# Stenophone.net
KiCad netlist of a schematic drawn in EAGLE
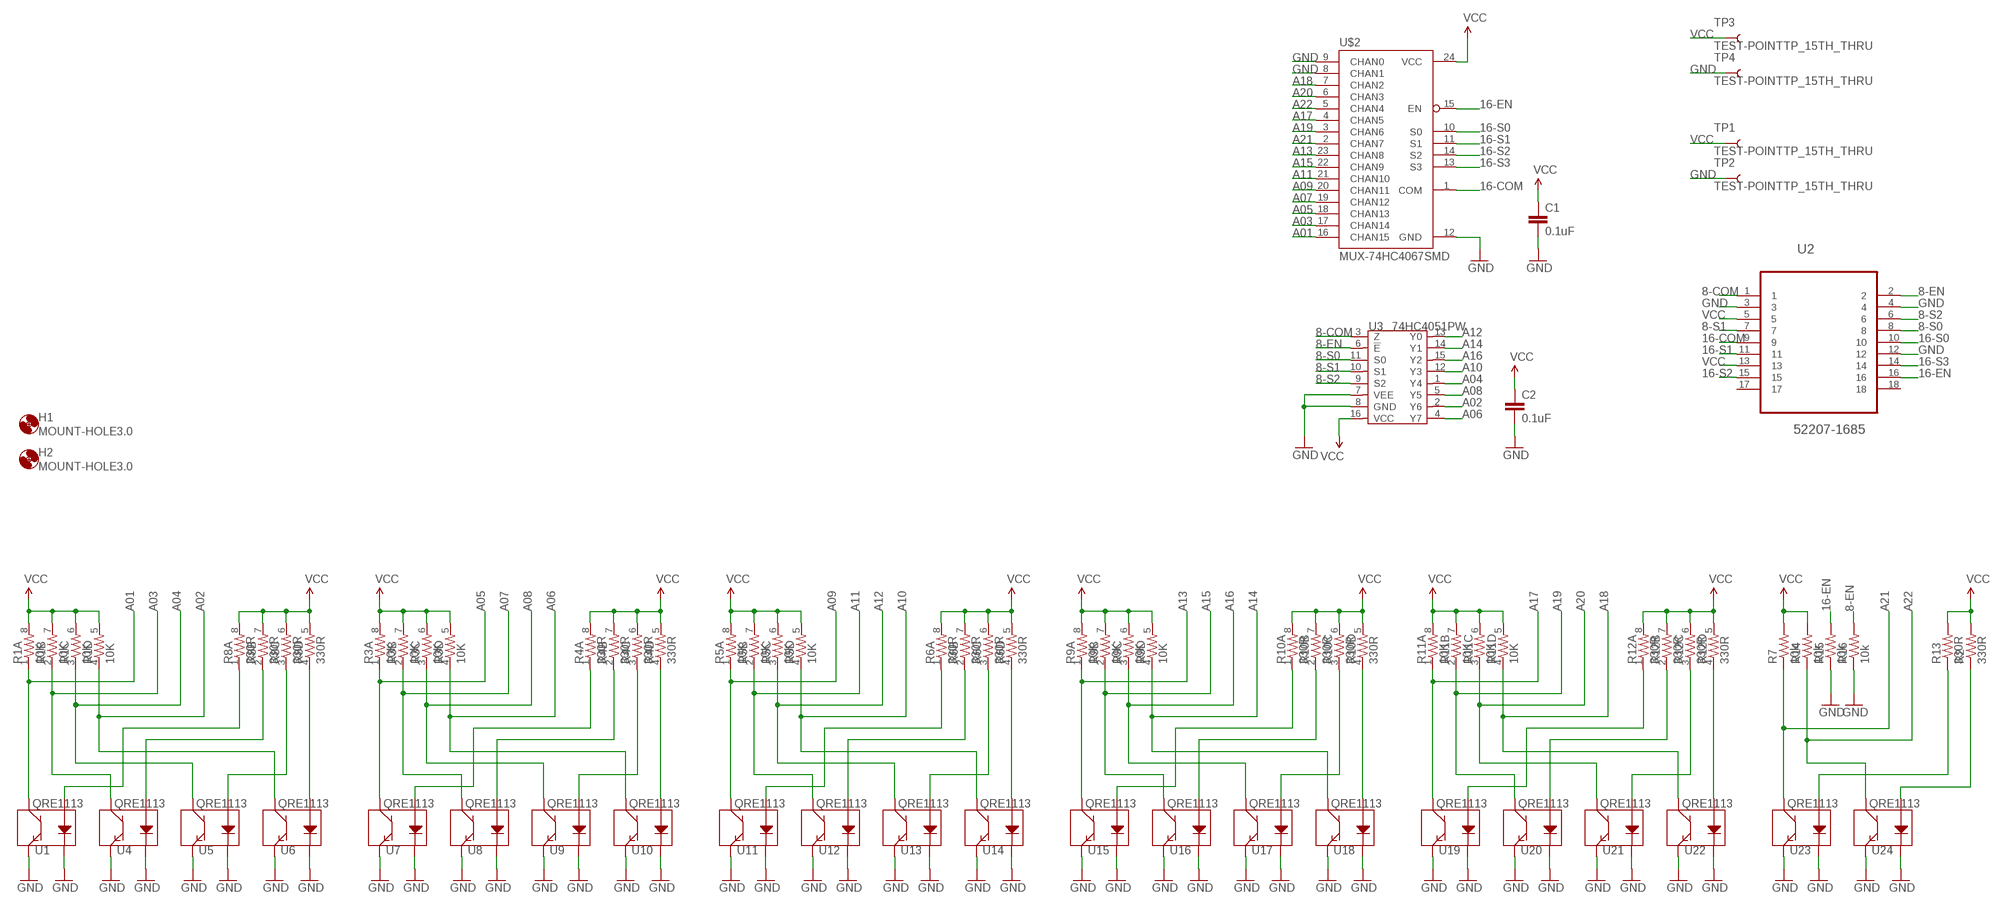
[diagram p0: schematic, sheet 1]

(export (version "E")
  (design (tool "Eeschema 10.0.6"))
  (components
    (comp (ref "C1")
      (value "0.1uF")
      (footprint "eagle-import:0603-CAP")
      (libsource (lib "eagle-import") (part "CAP0603-CAP"))
    )
    (comp (ref "C2")
      (value "0.1uF")
      (footprint "eagle-import:0603-CAP")
      (libsource (lib "eagle-import") (part "CAP0603-CAP"))
    )
    (comp (ref "H1")
      (value "MOUNT-HOLE3.0")
      (footprint "eagle-import:3,0")
      (libsource (lib "eagle-import") (part "MOUNT-HOLE3.0"))
    )
    (comp (ref "H2")
      (value "MOUNT-HOLE3.0")
      (footprint "eagle-import:3,0")
      (libsource (lib "eagle-import") (part "MOUNT-HOLE3.0"))
    )
    (comp (ref "R1")
      (value "10K")
      (footprint "eagle-import:0603-ARV")
      (libsource (lib "eagle-import") (part "RESISTOR-ARRAY0603-ARV"))
    )
    (comp (ref "R2")
      (value "330R")
      (footprint "eagle-import:0603-RES")
      (libsource (lib "eagle-import") (part "RESISTOR0603-RES"))
    )
    (comp (ref "R3")
      (value "10K")
      (footprint "eagle-import:0603-ARV")
      (libsource (lib "eagle-import") (part "RESISTOR-ARRAY0603-ARV"))
    )
    (comp (ref "R4")
      (value "330R")
      (footprint "eagle-import:0603-ARV")
      (libsource (lib "eagle-import") (part "RESISTOR-ARRAY0603-ARV"))
    )
    (comp (ref "R5")
      (value "10K")
      (footprint "eagle-import:0603-ARV")
      (libsource (lib "eagle-import") (part "RESISTOR-ARRAY0603-ARV"))
    )
    (comp (ref "R6")
      (value "330R")
      (footprint "eagle-import:0603-ARV")
      (libsource (lib "eagle-import") (part "RESISTOR-ARRAY0603-ARV"))
    )
    (comp (ref "R7")
      (value "10k")
      (footprint "eagle-import:0603-RES")
      (libsource (lib "eagle-import") (part "RESISTOR0603-RES"))
    )
    (comp (ref "R8")
      (value "330R")
      (footprint "eagle-import:0603-ARV")
      (libsource (lib "eagle-import") (part "RESISTOR-ARRAY0603-ARV"))
    )
    (comp (ref "R9")
      (value "10K")
      (footprint "eagle-import:0603-ARV")
      (libsource (lib "eagle-import") (part "RESISTOR-ARRAY0603-ARV"))
    )
    (comp (ref "R10")
      (value "330R")
      (footprint "eagle-import:0603-ARV")
      (libsource (lib "eagle-import") (part "RESISTOR-ARRAY0603-ARV"))
    )
    (comp (ref "R11")
      (value "10K")
      (footprint "eagle-import:0603-ARV")
      (libsource (lib "eagle-import") (part "RESISTOR-ARRAY0603-ARV"))
    )
    (comp (ref "R12")
      (value "330R")
      (footprint "eagle-import:0603-ARV")
      (libsource (lib "eagle-import") (part "RESISTOR-ARRAY0603-ARV"))
    )
    (comp (ref "R13")
      (value "330R")
      (footprint "eagle-import:0603-RES")
      (libsource (lib "eagle-import") (part "RESISTOR0603-RES"))
    )
    (comp (ref "R14")
      (value "10k")
      (footprint "eagle-import:0603-RES")
      (libsource (lib "eagle-import") (part "RESISTOR0603-RES"))
    )
    (comp (ref "R15")
      (value "10k")
      (footprint "eagle-import:0603-RES")
      (libsource (lib "eagle-import") (part "RESISTOR0603-RES"))
    )
    (comp (ref "R16")
      (value "10k")
      (footprint "eagle-import:0603-RES")
      (libsource (lib "eagle-import") (part "RESISTOR0603-RES"))
    )
    (comp (ref "TP1")
      (value "TEST-POINTTP_15TH_THRU")
      (footprint "eagle-import:TP_15TH")
      (libsource (lib "eagle-import") (part "TEST-POINTTP_15TH_THRU"))
    )
    (comp (ref "TP2")
      (value "TEST-POINTTP_15TH_THRU")
      (footprint "eagle-import:TP_15TH")
      (libsource (lib "eagle-import") (part "TEST-POINTTP_15TH_THRU"))
    )
    (comp (ref "TP3")
      (value "TEST-POINTTP_15TH_THRU")
      (footprint "eagle-import:TP_15TH")
      (libsource (lib "eagle-import") (part "TEST-POINTTP_15TH_THRU"))
    )
    (comp (ref "TP4")
      (value "TEST-POINTTP_15TH_THRU")
      (footprint "eagle-import:TP_15TH")
      (libsource (lib "eagle-import") (part "TEST-POINTTP_15TH_THRU"))
    )
    (comp (ref "U$2")
      (value "MUX-74HC4067SMD")
      (footprint "eagle-import:SSOP24")
      (libsource (lib "eagle-import") (part "MUX-74HC4067SMD"))
    )
    (comp (ref "U1")
      (value "QRE1113")
      (footprint "eagle-import:QRE1113")
      (libsource (lib "eagle-import") (part "QRE1113"))
    )
    (comp (ref "U2")
      (value "52207-1685")
      (footprint "eagle-import:MOLEX_52207-1685")
      (libsource (lib "eagle-import") (part "52207-1685"))
    )
    (comp (ref "U3")
      (value "74HC4051PW")
      (footprint "eagle-import:TSSOP16-6.6")
      (libsource (lib "eagle-import") (part "744051PWHC"))
    )
    (comp (ref "U4")
      (value "QRE1113")
      (footprint "eagle-import:QRE1113")
      (libsource (lib "eagle-import") (part "QRE1113"))
    )
    (comp (ref "U5")
      (value "QRE1113")
      (footprint "eagle-import:QRE1113")
      (libsource (lib "eagle-import") (part "QRE1113"))
    )
    (comp (ref "U6")
      (value "QRE1113")
      (footprint "eagle-import:QRE1113")
      (libsource (lib "eagle-import") (part "QRE1113"))
    )
    (comp (ref "U7")
      (value "QRE1113")
      (footprint "eagle-import:QRE1113")
      (libsource (lib "eagle-import") (part "QRE1113"))
    )
    (comp (ref "U8")
      (value "QRE1113")
      (footprint "eagle-import:QRE1113")
      (libsource (lib "eagle-import") (part "QRE1113"))
    )
    (comp (ref "U9")
      (value "QRE1113")
      (footprint "eagle-import:QRE1113")
      (libsource (lib "eagle-import") (part "QRE1113"))
    )
    (comp (ref "U10")
      (value "QRE1113")
      (footprint "eagle-import:QRE1113")
      (libsource (lib "eagle-import") (part "QRE1113"))
    )
    (comp (ref "U11")
      (value "QRE1113")
      (footprint "eagle-import:QRE1113")
      (libsource (lib "eagle-import") (part "QRE1113"))
    )
    (comp (ref "U12")
      (value "QRE1113")
      (footprint "eagle-import:QRE1113")
      (libsource (lib "eagle-import") (part "QRE1113"))
    )
    (comp (ref "U13")
      (value "QRE1113")
      (footprint "eagle-import:QRE1113")
      (libsource (lib "eagle-import") (part "QRE1113"))
    )
    (comp (ref "U14")
      (value "QRE1113")
      (footprint "eagle-import:QRE1113")
      (libsource (lib "eagle-import") (part "QRE1113"))
    )
    (comp (ref "U15")
      (value "QRE1113")
      (footprint "eagle-import:QRE1113")
      (libsource (lib "eagle-import") (part "QRE1113"))
    )
    (comp (ref "U16")
      (value "QRE1113")
      (footprint "eagle-import:QRE1113")
      (libsource (lib "eagle-import") (part "QRE1113"))
    )
    (comp (ref "U17")
      (value "QRE1113")
      (footprint "eagle-import:QRE1113")
      (libsource (lib "eagle-import") (part "QRE1113"))
    )
    (comp (ref "U18")
      (value "QRE1113")
      (footprint "eagle-import:QRE1113")
      (libsource (lib "eagle-import") (part "QRE1113"))
    )
    (comp (ref "U19")
      (value "QRE1113")
      (footprint "eagle-import:QRE1113")
      (libsource (lib "eagle-import") (part "QRE1113"))
    )
    (comp (ref "U20")
      (value "QRE1113")
      (footprint "eagle-import:QRE1113")
      (libsource (lib "eagle-import") (part "QRE1113"))
    )
    (comp (ref "U21")
      (value "QRE1113")
      (footprint "eagle-import:QRE1113")
      (libsource (lib "eagle-import") (part "QRE1113"))
    )
    (comp (ref "U22")
      (value "QRE1113")
      (footprint "eagle-import:QRE1113")
      (libsource (lib "eagle-import") (part "QRE1113"))
    )
    (comp (ref "U23")
      (value "QRE1113")
      (footprint "eagle-import:QRE1113")
      (libsource (lib "eagle-import") (part "QRE1113"))
    )
    (comp (ref "U24")
      (value "QRE1113")
      (footprint "eagle-import:QRE1113")
      (libsource (lib "eagle-import") (part "QRE1113"))
    )
  )
  (nets
    (net (code "1") (name "/8-COM") (class "Default")
      (node (ref "U2") (pin "1") (pinfunction "1_1") (pintype "passive"))
      (node (ref "U3") (pin "3") (pinfunction "Z_3") (pintype "bidirectional"))
    )
    (net (code "2") (name "/8-EN") (class "Default")
      (node (ref "R16") (pin "2") (pinfunction "2_2") (pintype "passive"))
      (node (ref "U2") (pin "2") (pinfunction "2_2") (pintype "passive"))
      (node (ref "U3") (pin "6") (pinfunction "~{E}_6") (pintype "bidirectional"))
    )
    (net (code "3") (name "/8-S0") (class "Default")
      (node (ref "U2") (pin "8") (pinfunction "8_8") (pintype "passive"))
      (node (ref "U3") (pin "11") (pinfunction "S0_11") (pintype "bidirectional"))
    )
    (net (code "4") (name "/8-S1") (class "Default")
      (node (ref "U2") (pin "7") (pinfunction "7_7") (pintype "passive"))
      (node (ref "U3") (pin "10") (pinfunction "S1_10") (pintype "bidirectional"))
    )
    (net (code "5") (name "/8-S2") (class "Default")
      (node (ref "U2") (pin "6") (pinfunction "6_6") (pintype "passive"))
      (node (ref "U3") (pin "9") (pinfunction "S2_9") (pintype "bidirectional"))
    )
    (net (code "6") (name "/16-COM") (class "Default")
      (node (ref "U$2") (pin "1") (pinfunction "COM_1") (pintype "bidirectional"))
      (node (ref "U2") (pin "9") (pinfunction "9_9") (pintype "passive"))
    )
    (net (code "7") (name "/16-EN") (class "Default")
      (node (ref "R15") (pin "2") (pinfunction "2_2") (pintype "passive"))
      (node (ref "U$2") (pin "15") (pinfunction "EN_15") (pintype "input"))
      (node (ref "U2") (pin "16") (pinfunction "16_16") (pintype "passive"))
    )
    (net (code "8") (name "/16-S0") (class "Default")
      (node (ref "U$2") (pin "10") (pinfunction "S0_10") (pintype "input"))
      (node (ref "U2") (pin "10") (pinfunction "10_10") (pintype "passive"))
    )
    (net (code "9") (name "/16-S1") (class "Default")
      (node (ref "U$2") (pin "11") (pinfunction "S1_11") (pintype "input"))
      (node (ref "U2") (pin "11") (pinfunction "11_11") (pintype "passive"))
    )
    (net (code "10") (name "/16-S2") (class "Default")
      (node (ref "U$2") (pin "14") (pinfunction "S2_14") (pintype "input"))
      (node (ref "U2") (pin "15") (pinfunction "15_15") (pintype "passive"))
    )
    (net (code "11") (name "/16-S3") (class "Default")
      (node (ref "U$2") (pin "13") (pinfunction "S3_13") (pintype "input"))
      (node (ref "U2") (pin "14") (pinfunction "14_14") (pintype "passive"))
    )
    (net (code "12") (name "/A01") (class "Default")
      (node (ref "R1") (pin "1") (pinfunction "1_1") (pintype "passive"))
      (node (ref "U$2") (pin "16") (pinfunction "CHAN15_16") (pintype "bidirectional"))
      (node (ref "U1") (pin "3") (pinfunction "C_3") (pintype "bidirectional"))
    )
    (net (code "13") (name "/A02") (class "Default")
      (node (ref "R1") (pin "4") (pinfunction "1_4") (pintype "passive"))
      (node (ref "U3") (pin "2") (pinfunction "Y6_2") (pintype "bidirectional"))
      (node (ref "U6") (pin "3") (pinfunction "C_3") (pintype "bidirectional"))
    )
    (net (code "14") (name "/A03") (class "Default")
      (node (ref "R1") (pin "2") (pinfunction "1_2") (pintype "passive"))
      (node (ref "U$2") (pin "17") (pinfunction "CHAN14_17") (pintype "bidirectional"))
      (node (ref "U4") (pin "3") (pinfunction "C_3") (pintype "bidirectional"))
    )
    (net (code "15") (name "/A04") (class "Default")
      (node (ref "R1") (pin "3") (pinfunction "1_3") (pintype "passive"))
      (node (ref "U3") (pin "1") (pinfunction "Y4_1") (pintype "bidirectional"))
      (node (ref "U5") (pin "3") (pinfunction "C_3") (pintype "bidirectional"))
    )
    (net (code "16") (name "/A05") (class "Default")
      (node (ref "R3") (pin "1") (pinfunction "1_1") (pintype "passive"))
      (node (ref "U$2") (pin "18") (pinfunction "CHAN13_18") (pintype "bidirectional"))
      (node (ref "U7") (pin "3") (pinfunction "C_3") (pintype "bidirectional"))
    )
    (net (code "17") (name "/A06") (class "Default")
      (node (ref "R3") (pin "4") (pinfunction "1_4") (pintype "passive"))
      (node (ref "U10") (pin "3") (pinfunction "C_3") (pintype "bidirectional"))
      (node (ref "U3") (pin "4") (pinfunction "Y7_4") (pintype "bidirectional"))
    )
    (net (code "18") (name "/A07") (class "Default")
      (node (ref "R3") (pin "2") (pinfunction "1_2") (pintype "passive"))
      (node (ref "U$2") (pin "19") (pinfunction "CHAN12_19") (pintype "bidirectional"))
      (node (ref "U8") (pin "3") (pinfunction "C_3") (pintype "bidirectional"))
    )
    (net (code "19") (name "/A08") (class "Default")
      (node (ref "R3") (pin "3") (pinfunction "1_3") (pintype "passive"))
      (node (ref "U3") (pin "5") (pinfunction "Y5_5") (pintype "bidirectional"))
      (node (ref "U9") (pin "3") (pinfunction "C_3") (pintype "bidirectional"))
    )
    (net (code "20") (name "/A09") (class "Default")
      (node (ref "R5") (pin "1") (pinfunction "1_1") (pintype "passive"))
      (node (ref "U$2") (pin "20") (pinfunction "CHAN11_20") (pintype "bidirectional"))
      (node (ref "U11") (pin "3") (pinfunction "C_3") (pintype "bidirectional"))
    )
    (net (code "21") (name "/A10") (class "Default")
      (node (ref "R5") (pin "4") (pinfunction "1_4") (pintype "passive"))
      (node (ref "U14") (pin "3") (pinfunction "C_3") (pintype "bidirectional"))
      (node (ref "U3") (pin "12") (pinfunction "Y3_12") (pintype "bidirectional"))
    )
    (net (code "22") (name "/A11") (class "Default")
      (node (ref "R5") (pin "2") (pinfunction "1_2") (pintype "passive"))
      (node (ref "U$2") (pin "21") (pinfunction "CHAN10_21") (pintype "bidirectional"))
      (node (ref "U12") (pin "3") (pinfunction "C_3") (pintype "bidirectional"))
    )
    (net (code "23") (name "/A12") (class "Default")
      (node (ref "R5") (pin "3") (pinfunction "1_3") (pintype "passive"))
      (node (ref "U13") (pin "3") (pinfunction "C_3") (pintype "bidirectional"))
      (node (ref "U3") (pin "13") (pinfunction "Y0_13") (pintype "bidirectional"))
    )
    (net (code "24") (name "/A13") (class "Default")
      (node (ref "R9") (pin "1") (pinfunction "1_1") (pintype "passive"))
      (node (ref "U$2") (pin "23") (pinfunction "CHAN8_23") (pintype "bidirectional"))
      (node (ref "U15") (pin "3") (pinfunction "C_3") (pintype "bidirectional"))
    )
    (net (code "25") (name "/A14") (class "Default")
      (node (ref "R9") (pin "4") (pinfunction "1_4") (pintype "passive"))
      (node (ref "U18") (pin "3") (pinfunction "C_3") (pintype "bidirectional"))
      (node (ref "U3") (pin "14") (pinfunction "Y1_14") (pintype "bidirectional"))
    )
    (net (code "26") (name "/A15") (class "Default")
      (node (ref "R9") (pin "2") (pinfunction "1_2") (pintype "passive"))
      (node (ref "U$2") (pin "22") (pinfunction "CHAN9_22") (pintype "bidirectional"))
      (node (ref "U16") (pin "3") (pinfunction "C_3") (pintype "bidirectional"))
    )
    (net (code "27") (name "/A16") (class "Default")
      (node (ref "R9") (pin "3") (pinfunction "1_3") (pintype "passive"))
      (node (ref "U17") (pin "3") (pinfunction "C_3") (pintype "bidirectional"))
      (node (ref "U3") (pin "15") (pinfunction "Y2_15") (pintype "bidirectional"))
    )
    (net (code "28") (name "/A17") (class "Default")
      (node (ref "R11") (pin "1") (pinfunction "1_1") (pintype "passive"))
      (node (ref "U$2") (pin "4") (pinfunction "CHAN5_4") (pintype "bidirectional"))
      (node (ref "U19") (pin "3") (pinfunction "C_3") (pintype "bidirectional"))
    )
    (net (code "29") (name "/A18") (class "Default")
      (node (ref "R11") (pin "4") (pinfunction "1_4") (pintype "passive"))
      (node (ref "U$2") (pin "7") (pinfunction "CHAN2_7") (pintype "bidirectional"))
      (node (ref "U22") (pin "3") (pinfunction "C_3") (pintype "bidirectional"))
    )
    (net (code "30") (name "/A19") (class "Default")
      (node (ref "R11") (pin "2") (pinfunction "1_2") (pintype "passive"))
      (node (ref "U$2") (pin "3") (pinfunction "CHAN6_3") (pintype "bidirectional"))
      (node (ref "U20") (pin "3") (pinfunction "C_3") (pintype "bidirectional"))
    )
    (net (code "31") (name "/A20") (class "Default")
      (node (ref "R11") (pin "3") (pinfunction "1_3") (pintype "passive"))
      (node (ref "U$2") (pin "6") (pinfunction "CHAN3_6") (pintype "bidirectional"))
      (node (ref "U21") (pin "3") (pinfunction "C_3") (pintype "bidirectional"))
    )
    (net (code "32") (name "/A21") (class "Default")
      (node (ref "R7") (pin "1") (pinfunction "1_1") (pintype "passive"))
      (node (ref "U$2") (pin "2") (pinfunction "CHAN7_2") (pintype "bidirectional"))
      (node (ref "U23") (pin "3") (pinfunction "C_3") (pintype "bidirectional"))
    )
    (net (code "33") (name "/A22") (class "Default")
      (node (ref "R14") (pin "1") (pinfunction "1_1") (pintype "passive"))
      (node (ref "U$2") (pin "5") (pinfunction "CHAN4_5") (pintype "bidirectional"))
      (node (ref "U24") (pin "3") (pinfunction "C_3") (pintype "bidirectional"))
    )
    (net (code "34") (name "GND") (class "Default")
      (node (ref "C1") (pin "2") (pinfunction "2_2") (pintype "passive"))
      (node (ref "C2") (pin "2") (pinfunction "2_2") (pintype "passive"))
      (node (ref "R15") (pin "1") (pinfunction "1_1") (pintype "passive"))
      (node (ref "R16") (pin "1") (pinfunction "1_1") (pintype "passive"))
      (node (ref "TP2") (pin "P$1") (pinfunction "1_P$1") (pintype "bidirectional"))
      (node (ref "TP4") (pin "P$1") (pinfunction "1_P$1") (pintype "bidirectional"))
      (node (ref "U$2") (pin "12") (pinfunction "GND_12") (pintype "bidirectional"))
      (node (ref "U$2") (pin "8") (pinfunction "CHAN1_8") (pintype "bidirectional"))
      (node (ref "U$2") (pin "9") (pinfunction "CHAN0_9") (pintype "bidirectional"))
      (node (ref "U1") (pin "2") (pinfunction "K_2") (pintype "bidirectional"))
      (node (ref "U1") (pin "4") (pinfunction "E_4") (pintype "bidirectional"))
      (node (ref "U10") (pin "2") (pinfunction "K_2") (pintype "bidirectional"))
      (node (ref "U10") (pin "4") (pinfunction "E_4") (pintype "bidirectional"))
      (node (ref "U11") (pin "2") (pinfunction "K_2") (pintype "bidirectional"))
      (node (ref "U11") (pin "4") (pinfunction "E_4") (pintype "bidirectional"))
      (node (ref "U12") (pin "2") (pinfunction "K_2") (pintype "bidirectional"))
      (node (ref "U12") (pin "4") (pinfunction "E_4") (pintype "bidirectional"))
      (node (ref "U13") (pin "2") (pinfunction "K_2") (pintype "bidirectional"))
      (node (ref "U13") (pin "4") (pinfunction "E_4") (pintype "bidirectional"))
      (node (ref "U14") (pin "2") (pinfunction "K_2") (pintype "bidirectional"))
      (node (ref "U14") (pin "4") (pinfunction "E_4") (pintype "bidirectional"))
      (node (ref "U15") (pin "2") (pinfunction "K_2") (pintype "bidirectional"))
      (node (ref "U15") (pin "4") (pinfunction "E_4") (pintype "bidirectional"))
      (node (ref "U16") (pin "2") (pinfunction "K_2") (pintype "bidirectional"))
      (node (ref "U16") (pin "4") (pinfunction "E_4") (pintype "bidirectional"))
      (node (ref "U17") (pin "2") (pinfunction "K_2") (pintype "bidirectional"))
      (node (ref "U17") (pin "4") (pinfunction "E_4") (pintype "bidirectional"))
      (node (ref "U18") (pin "2") (pinfunction "K_2") (pintype "bidirectional"))
      (node (ref "U18") (pin "4") (pinfunction "E_4") (pintype "bidirectional"))
      (node (ref "U19") (pin "2") (pinfunction "K_2") (pintype "bidirectional"))
      (node (ref "U19") (pin "4") (pinfunction "E_4") (pintype "bidirectional"))
      (node (ref "U2") (pin "12") (pinfunction "12_12") (pintype "passive"))
      (node (ref "U2") (pin "3") (pinfunction "3_3") (pintype "passive"))
      (node (ref "U2") (pin "4") (pinfunction "4_4") (pintype "passive"))
      (node (ref "U20") (pin "2") (pinfunction "K_2") (pintype "bidirectional"))
      (node (ref "U20") (pin "4") (pinfunction "E_4") (pintype "bidirectional"))
      (node (ref "U21") (pin "2") (pinfunction "K_2") (pintype "bidirectional"))
      (node (ref "U21") (pin "4") (pinfunction "E_4") (pintype "bidirectional"))
      (node (ref "U22") (pin "2") (pinfunction "K_2") (pintype "bidirectional"))
      (node (ref "U22") (pin "4") (pinfunction "E_4") (pintype "bidirectional"))
      (node (ref "U23") (pin "2") (pinfunction "K_2") (pintype "bidirectional"))
      (node (ref "U23") (pin "4") (pinfunction "E_4") (pintype "bidirectional"))
      (node (ref "U24") (pin "2") (pinfunction "K_2") (pintype "bidirectional"))
      (node (ref "U24") (pin "4") (pinfunction "E_4") (pintype "bidirectional"))
      (node (ref "U3") (pin "7") (pinfunction "VEE_7") (pintype "bidirectional"))
      (node (ref "U3") (pin "8") (pinfunction "GND_8") (pintype "power_in"))
      (node (ref "U4") (pin "2") (pinfunction "K_2") (pintype "bidirectional"))
      (node (ref "U4") (pin "4") (pinfunction "E_4") (pintype "bidirectional"))
      (node (ref "U5") (pin "2") (pinfunction "K_2") (pintype "bidirectional"))
      (node (ref "U5") (pin "4") (pinfunction "E_4") (pintype "bidirectional"))
      (node (ref "U6") (pin "2") (pinfunction "K_2") (pintype "bidirectional"))
      (node (ref "U6") (pin "4") (pinfunction "E_4") (pintype "bidirectional"))
      (node (ref "U7") (pin "2") (pinfunction "K_2") (pintype "bidirectional"))
      (node (ref "U7") (pin "4") (pinfunction "E_4") (pintype "bidirectional"))
      (node (ref "U8") (pin "2") (pinfunction "K_2") (pintype "bidirectional"))
      (node (ref "U8") (pin "4") (pinfunction "E_4") (pintype "bidirectional"))
      (node (ref "U9") (pin "2") (pinfunction "K_2") (pintype "bidirectional"))
      (node (ref "U9") (pin "4") (pinfunction "E_4") (pintype "bidirectional"))
    )
    (net (code "35") (name "Net-(R4B-1)") (class "Default")
      (node (ref "R4") (pin "2") (pinfunction "1_2") (pintype "passive"))
      (node (ref "U8") (pin "1") (pinfunction "A_1") (pintype "bidirectional"))
    )
    (net (code "36") (name "Net-(R4C-1)") (class "Default")
      (node (ref "R4") (pin "3") (pinfunction "1_3") (pintype "passive"))
      (node (ref "U9") (pin "1") (pinfunction "A_1") (pintype "bidirectional"))
    )
    (net (code "37") (name "Net-(R4D-1)") (class "Default")
      (node (ref "R4") (pin "4") (pinfunction "1_4") (pintype "passive"))
      (node (ref "U10") (pin "1") (pinfunction "A_1") (pintype "bidirectional"))
    )
    (net (code "38") (name "Net-(R6B-1)") (class "Default")
      (node (ref "R6") (pin "2") (pinfunction "1_2") (pintype "passive"))
      (node (ref "U12") (pin "1") (pinfunction "A_1") (pintype "bidirectional"))
    )
    (net (code "39") (name "Net-(R6C-1)") (class "Default")
      (node (ref "R6") (pin "3") (pinfunction "1_3") (pintype "passive"))
      (node (ref "U13") (pin "1") (pinfunction "A_1") (pintype "bidirectional"))
    )
    (net (code "40") (name "Net-(R6D-1)") (class "Default")
      (node (ref "R6") (pin "4") (pinfunction "1_4") (pintype "passive"))
      (node (ref "U14") (pin "1") (pinfunction "A_1") (pintype "bidirectional"))
    )
    (net (code "41") (name "Net-(R8B-1)") (class "Default")
      (node (ref "R8") (pin "2") (pinfunction "1_2") (pintype "passive"))
      (node (ref "U4") (pin "1") (pinfunction "A_1") (pintype "bidirectional"))
    )
    (net (code "42") (name "Net-(R8C-1)") (class "Default")
      (node (ref "R8") (pin "3") (pinfunction "1_3") (pintype "passive"))
      (node (ref "U5") (pin "1") (pinfunction "A_1") (pintype "bidirectional"))
    )
    (net (code "43") (name "Net-(R8D-1)") (class "Default")
      (node (ref "R8") (pin "4") (pinfunction "1_4") (pintype "passive"))
      (node (ref "U6") (pin "1") (pinfunction "A_1") (pintype "bidirectional"))
    )
    (net (code "44") (name "Net-(R10B-1)") (class "Default")
      (node (ref "R10") (pin "2") (pinfunction "1_2") (pintype "passive"))
      (node (ref "U16") (pin "1") (pinfunction "A_1") (pintype "bidirectional"))
    )
    (net (code "45") (name "Net-(R10C-1)") (class "Default")
      (node (ref "R10") (pin "3") (pinfunction "1_3") (pintype "passive"))
      (node (ref "U17") (pin "1") (pinfunction "A_1") (pintype "bidirectional"))
    )
    (net (code "46") (name "Net-(R10D-1)") (class "Default")
      (node (ref "R10") (pin "4") (pinfunction "1_4") (pintype "passive"))
      (node (ref "U18") (pin "1") (pinfunction "A_1") (pintype "bidirectional"))
    )
    (net (code "47") (name "Net-(R12B-1)") (class "Default")
      (node (ref "R12") (pin "2") (pinfunction "1_2") (pintype "passive"))
      (node (ref "U20") (pin "1") (pinfunction "A_1") (pintype "bidirectional"))
    )
    (net (code "48") (name "Net-(R12C-1)") (class "Default")
      (node (ref "R12") (pin "3") (pinfunction "1_3") (pintype "passive"))
      (node (ref "U21") (pin "1") (pinfunction "A_1") (pintype "bidirectional"))
    )
    (net (code "49") (name "Net-(R12D-1)") (class "Default")
      (node (ref "R12") (pin "4") (pinfunction "1_4") (pintype "passive"))
      (node (ref "U22") (pin "1") (pinfunction "A_1") (pintype "bidirectional"))
    )
    (net (code "50") (name "Net-(U1-A)") (class "Default")
      (node (ref "R8") (pin "1") (pinfunction "1_1") (pintype "passive"))
      (node (ref "U1") (pin "1") (pinfunction "A_1") (pintype "bidirectional"))
    )
    (net (code "51") (name "Net-(U7-A)") (class "Default")
      (node (ref "R4") (pin "1") (pinfunction "1_1") (pintype "passive"))
      (node (ref "U7") (pin "1") (pinfunction "A_1") (pintype "bidirectional"))
    )
    (net (code "52") (name "Net-(U11-A)") (class "Default")
      (node (ref "R6") (pin "1") (pinfunction "1_1") (pintype "passive"))
      (node (ref "U11") (pin "1") (pinfunction "A_1") (pintype "bidirectional"))
    )
    (net (code "53") (name "Net-(U15-A)") (class "Default")
      (node (ref "R10") (pin "1") (pinfunction "1_1") (pintype "passive"))
      (node (ref "U15") (pin "1") (pinfunction "A_1") (pintype "bidirectional"))
    )
    (net (code "54") (name "Net-(U19-A)") (class "Default")
      (node (ref "R12") (pin "1") (pinfunction "1_1") (pintype "passive"))
      (node (ref "U19") (pin "1") (pinfunction "A_1") (pintype "bidirectional"))
    )
    (net (code "55") (name "Net-(U23-A)") (class "Default")
      (node (ref "R13") (pin "1") (pinfunction "1_1") (pintype "passive"))
      (node (ref "U23") (pin "1") (pinfunction "A_1") (pintype "bidirectional"))
    )
    (net (code "56") (name "Net-(U24-A)") (class "Default")
      (node (ref "R2") (pin "1") (pinfunction "1_1") (pintype "passive"))
      (node (ref "U24") (pin "1") (pinfunction "A_1") (pintype "bidirectional"))
    )
    (net (code "57") (name "VCC") (class "Default")
      (node (ref "C1") (pin "1") (pinfunction "1_1") (pintype "passive"))
      (node (ref "C2") (pin "1") (pinfunction "1_1") (pintype "passive"))
      (node (ref "R1") (pin "5") (pinfunction "2_5") (pintype "passive"))
      (node (ref "R1") (pin "6") (pinfunction "2_6") (pintype "passive"))
      (node (ref "R1") (pin "7") (pinfunction "2_7") (pintype "passive"))
      (node (ref "R1") (pin "8") (pinfunction "2_8") (pintype "passive"))
      (node (ref "R10") (pin "5") (pinfunction "2_5") (pintype "passive"))
      (node (ref "R10") (pin "6") (pinfunction "2_6") (pintype "passive"))
      (node (ref "R10") (pin "7") (pinfunction "2_7") (pintype "passive"))
      (node (ref "R10") (pin "8") (pinfunction "2_8") (pintype "passive"))
      (node (ref "R11") (pin "5") (pinfunction "2_5") (pintype "passive"))
      (node (ref "R11") (pin "6") (pinfunction "2_6") (pintype "passive"))
      (node (ref "R11") (pin "7") (pinfunction "2_7") (pintype "passive"))
      (node (ref "R11") (pin "8") (pinfunction "2_8") (pintype "passive"))
      (node (ref "R12") (pin "5") (pinfunction "2_5") (pintype "passive"))
      (node (ref "R12") (pin "6") (pinfunction "2_6") (pintype "passive"))
      (node (ref "R12") (pin "7") (pinfunction "2_7") (pintype "passive"))
      (node (ref "R12") (pin "8") (pinfunction "2_8") (pintype "passive"))
      (node (ref "R13") (pin "2") (pinfunction "2_2") (pintype "passive"))
      (node (ref "R14") (pin "2") (pinfunction "2_2") (pintype "passive"))
      (node (ref "R2") (pin "2") (pinfunction "2_2") (pintype "passive"))
      (node (ref "R3") (pin "5") (pinfunction "2_5") (pintype "passive"))
      (node (ref "R3") (pin "6") (pinfunction "2_6") (pintype "passive"))
      (node (ref "R3") (pin "7") (pinfunction "2_7") (pintype "passive"))
      (node (ref "R3") (pin "8") (pinfunction "2_8") (pintype "passive"))
      (node (ref "R4") (pin "5") (pinfunction "2_5") (pintype "passive"))
      (node (ref "R4") (pin "6") (pinfunction "2_6") (pintype "passive"))
      (node (ref "R4") (pin "7") (pinfunction "2_7") (pintype "passive"))
      (node (ref "R4") (pin "8") (pinfunction "2_8") (pintype "passive"))
      (node (ref "R5") (pin "5") (pinfunction "2_5") (pintype "passive"))
      (node (ref "R5") (pin "6") (pinfunction "2_6") (pintype "passive"))
      (node (ref "R5") (pin "7") (pinfunction "2_7") (pintype "passive"))
      (node (ref "R5") (pin "8") (pinfunction "2_8") (pintype "passive"))
      (node (ref "R6") (pin "5") (pinfunction "2_5") (pintype "passive"))
      (node (ref "R6") (pin "6") (pinfunction "2_6") (pintype "passive"))
      (node (ref "R6") (pin "7") (pinfunction "2_7") (pintype "passive"))
      (node (ref "R6") (pin "8") (pinfunction "2_8") (pintype "passive"))
      (node (ref "R7") (pin "2") (pinfunction "2_2") (pintype "passive"))
      (node (ref "R8") (pin "5") (pinfunction "2_5") (pintype "passive"))
      (node (ref "R8") (pin "6") (pinfunction "2_6") (pintype "passive"))
      (node (ref "R8") (pin "7") (pinfunction "2_7") (pintype "passive"))
      (node (ref "R8") (pin "8") (pinfunction "2_8") (pintype "passive"))
      (node (ref "R9") (pin "5") (pinfunction "2_5") (pintype "passive"))
      (node (ref "R9") (pin "6") (pinfunction "2_6") (pintype "passive"))
      (node (ref "R9") (pin "7") (pinfunction "2_7") (pintype "passive"))
      (node (ref "R9") (pin "8") (pinfunction "2_8") (pintype "passive"))
      (node (ref "TP1") (pin "P$1") (pinfunction "1_P$1") (pintype "bidirectional"))
      (node (ref "TP3") (pin "P$1") (pinfunction "1_P$1") (pintype "bidirectional"))
      (node (ref "U$2") (pin "24") (pinfunction "VCC_24") (pintype "bidirectional"))
      (node (ref "U2") (pin "13") (pinfunction "13_13") (pintype "passive"))
      (node (ref "U2") (pin "5") (pinfunction "5_5") (pintype "passive"))
      (node (ref "U3") (pin "16") (pinfunction "VCC_16") (pintype "power_in"))
    )
    (net (code "58") (name "unconnected-(U2-Pad17)") (class "Default")
      (node (ref "U2") (pin "17") (pinfunction "17_17") (pintype "passive"))
    )
    (net (code "59") (name "unconnected-(U2-Pad18)") (class "Default")
      (node (ref "U2") (pin "18") (pinfunction "18_18") (pintype "passive"))
    )
  )
)
